# AUX_power_board.net
KiCad netlist of a schematic drawn in EAGLE
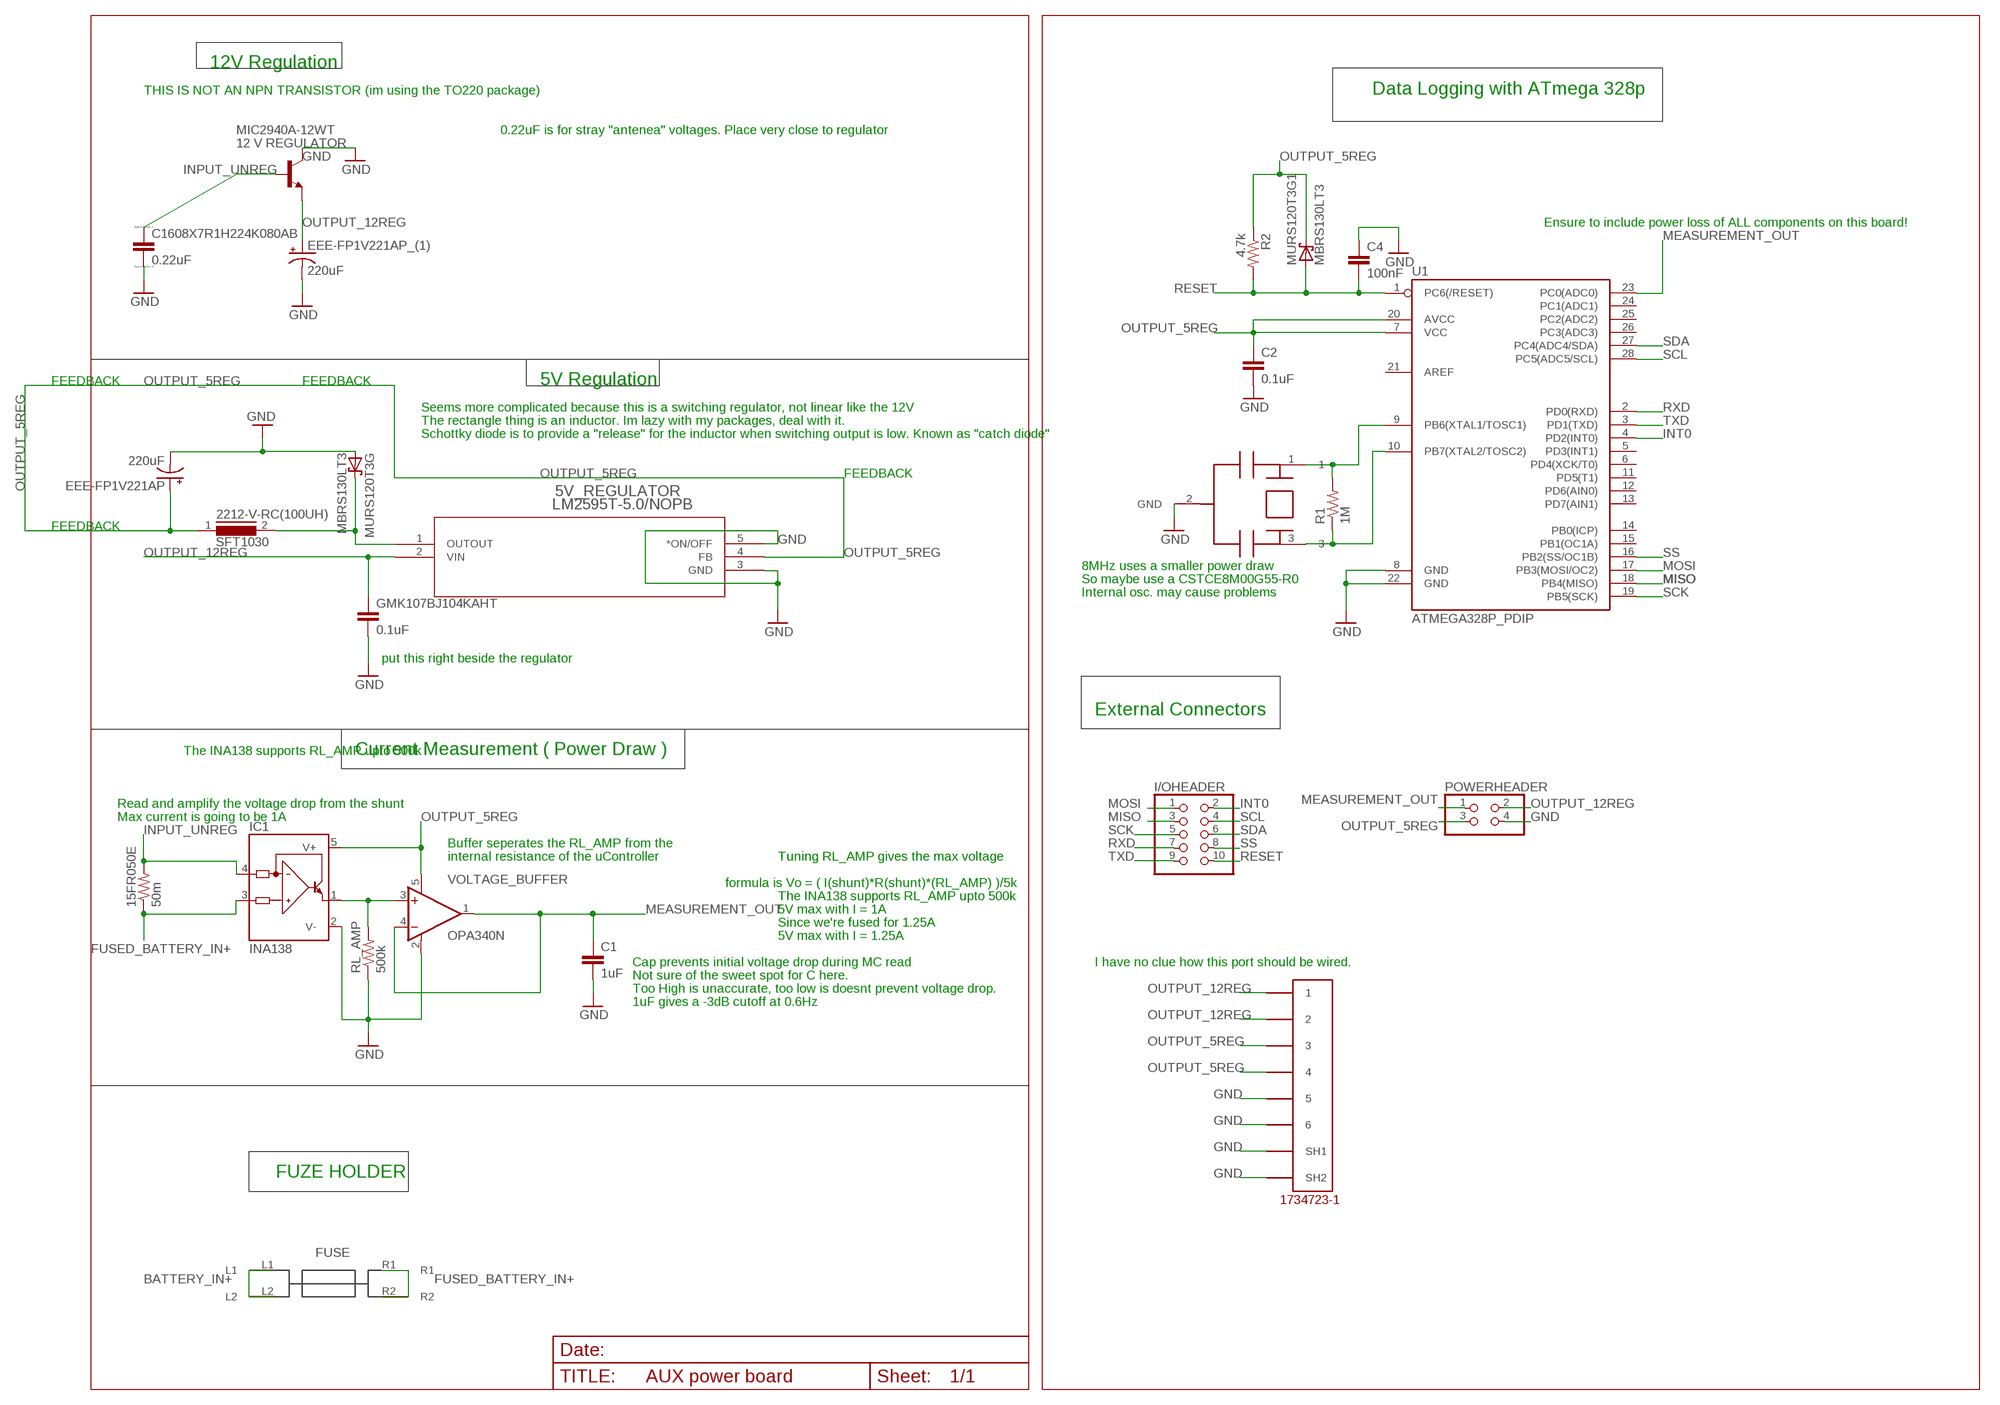
[diagram p0: schematic, sheet 1]

(export (version "E")
  (design (tool "Eeschema 10.0.6"))
  (components
    (comp (ref "5V_REGULATOR")
      (value "LM2595T-5.0/NOPB")
      (footprint "eagle-import:T05D")
      (fields
        (field (name "MANUFACTURER_PART_NUMBER") "LM2595T50")
        (field (name "COPYRIGHT") "Copyright C 2015 Accelerated Designs. All rights reserved")
      )
      (libsource (lib "eagle-import") (part "LM2595T-5.0/NOPB"))
    )
    (comp (ref "15FR050E")
      (value "50m")
      (footprint "eagle-import:0617_22")
      (libsource (lib "eagle-import") (part "resistor_R-US_0617/22"))
    )
    (comp (ref "2212-V-RC(100UH)")
      (value "SFT1030")
      (footprint "eagle-import:SFT1030")
      (libsource (lib "eagle-import") (part "SFT1030"))
    )
    (comp (ref "C1")
      (value "1uF")
      (footprint "eagle-import:C0603")
      (libsource (lib "eagle-import") (part "resistor_C-EUC0603"))
    )
    (comp (ref "C2")
      (value "0.1uF")
      (footprint "eagle-import:C0603")
      (libsource (lib "eagle-import") (part "resistor_C-EUC0603"))
    )
    (comp (ref "C4")
      (value "100nF")
      (footprint "eagle-import:C0603")
      (libsource (lib "eagle-import") (part "C-EUC0603"))
    )
    (comp (ref "C1608X7R1H224K080AB")
      (value "0.22uF")
      (footprint "eagle-import:C0603")
      (libsource (lib "eagle-import") (part "CC0603"))
    )
    (comp (ref "EEE-FP1V221AP")
      (value "220uF")
      (footprint "eagle-import:175TMP-0808")
      (libsource (lib "eagle-import") (part "CPOL-US175TMP-0808"))
    )
    (comp (ref "EEE-FP1V221AP_(1)")
      (value "220uF")
      (footprint "eagle-import:175TMP-0808")
      (libsource (lib "eagle-import") (part "CPOL-US175TMP-0808"))
    )
    (comp (ref "GMK107BJ104KAHT")
      (value "0.1uF")
      (footprint "eagle-import:C0603")
      (libsource (lib "eagle-import") (part "C-EUC0603"))
    )
    (comp (ref "I/OHEADER")
      (value "PINHD-2X5")
      (footprint "eagle-import:2X05")
      (libsource (lib "eagle-import") (part "PINHD-2X5"))
    )
    (comp (ref "IC1")
      (value "INA138")
      (footprint "eagle-import:SOT23-5")
      (fields (field (name "MF") "TEXAS INSTRUMENTS") (field (name "MPN") "INA138NA/250"))
      (libsource (lib "eagle-import") (part "INA138"))
    )
    (comp (ref "MIC2940A-12WT")
      (value "12 V REGULATOR")
      (footprint "eagle-import:TO220")
      (libsource (lib "eagle-import") (part "-NPN-TO220"))
    )
    (comp (ref "MINIBLADE")
      (value "3568")
      (footprint "eagle-import:3568")
      (libsource (lib "eagle-import") (part "3568"))
    )
    (comp (ref "MURS120T3G")
      (value "MBRS130LT3")
      (footprint "eagle-import:SMB")
      (libsource (lib "eagle-import") (part "MBRS130LT3"))
    )
    (comp (ref "MURS120T3G1")
      (value "MBRS130LT3")
      (footprint "eagle-import:SMB")
      (libsource (lib "eagle-import") (part "MBRS130LT3"))
    )
    (comp (ref "POWERHEADER")
      (value "PINHD-2X2")
      (footprint "eagle-import:2X02")
      (libsource (lib "eagle-import") (part "PINHD-2X2"))
    )
    (comp (ref "R1")
      (value "1M")
      (footprint "eagle-import:R0603")
      (libsource (lib "eagle-import") (part "R-US_R0603"))
    )
    (comp (ref "R2")
      (value "4.7k")
      (footprint "eagle-import:R0603")
      (libsource (lib "eagle-import") (part "resistor_R-US_R0603"))
    )
    (comp (ref "RL_AMP")
      (value "500k")
      (footprint "eagle-import:R0603")
      (libsource (lib "eagle-import") (part "resistor_R-US_R0603"))
    )
    (comp (ref "U$1")
      (value "CSTCE16M0V53-R0")
      (footprint "eagle-import:RESONATOR")
      (libsource (lib "eagle-import") (part "CSTCE16M0V53-R0"))
    )
    (comp (ref "U$3")
      (value "5555140-6")
      (footprint "eagle-import:1734723-1_RJ11")
      (libsource (lib "eagle-import") (part "5555140-6"))
    )
    (comp (ref "U1")
      (value "ATMEGA328P_PDIP")
      (footprint "eagle-import:DIL28-3")
      (libsource (lib "eagle-import") (part "ATMEGA328P_PDIP"))
    )
    (comp (ref "VOLTAGE_BUFFER")
      (value "OPA340N")
      (footprint "eagle-import:SOT23-5")
      (fields (field (name "MPN") "OPA340NA/3KG4"))
      (libsource (lib "eagle-import") (part "OPA340N"))
    )
  )
  (nets
    (net (code "1") (name "/BATTERY_IN+") (class "Default")
      (node (ref "MINIBLADE") (pin "L1") (pinfunction "L1_L1") (pintype "bidirectional"))
      (node (ref "MINIBLADE") (pin "L2") (pinfunction "L2_L2") (pintype "bidirectional"))
    )
    (net (code "2") (name "/FUSED_BATTERY_IN+") (class "Default")
      (node (ref "15FR050E") (pin "1") (pinfunction "1_1") (pintype "passive"))
      (node (ref "IC1") (pin "3") (pinfunction "IN+_3") (pintype "input"))
      (node (ref "MINIBLADE") (pin "R1") (pinfunction "R1_R1") (pintype "bidirectional"))
      (node (ref "MINIBLADE") (pin "R2") (pinfunction "R2_R2") (pintype "bidirectional"))
    )
    (net (code "3") (name "/INPUT_UNREG") (class "Default")
      (node (ref "15FR050E") (pin "2") (pinfunction "2_2") (pintype "passive"))
      (node (ref "C1608X7R1H224K080AB") (pin "1") (pinfunction "1_1") (pintype "passive"))
      (node (ref "IC1") (pin "4") (pinfunction "IN-_4") (pintype "input"))
      (node (ref "MIC2940A-12WT") (pin "1") (pinfunction "B_1") (pintype "passive"))
    )
    (net (code "4") (name "/INT0") (class "Default")
      (node (ref "I/OHEADER") (pin "2") (pinfunction "2_2") (pintype "passive"))
      (node (ref "U1") (pin "4") (pinfunction "PD2(INT0)_4") (pintype "bidirectional"))
    )
    (net (code "5") (name "/MEASUREMENT_OUT") (class "Default")
      (node (ref "C1") (pin "1") (pinfunction "1_1") (pintype "passive"))
      (node (ref "POWERHEADER") (pin "1") (pinfunction "1_1") (pintype "passive"))
      (node (ref "U1") (pin "23") (pinfunction "PC0(ADC0)_23") (pintype "bidirectional"))
      (node (ref "VOLTAGE_BUFFER") (pin "1") (pinfunction "OUT_1") (pintype "output"))
      (node (ref "VOLTAGE_BUFFER") (pin "4") (pinfunction "-IN_4") (pintype "input"))
    )
    (net (code "6") (name "/MISO") (class "Default")
      (node (ref "I/OHEADER") (pin "3") (pinfunction "3_3") (pintype "passive"))
      (node (ref "U1") (pin "18") (pinfunction "PB4(MISO)_18") (pintype "bidirectional"))
    )
    (net (code "7") (name "/MOSI") (class "Default")
      (node (ref "I/OHEADER") (pin "1") (pinfunction "1_1") (pintype "passive"))
      (node (ref "U1") (pin "17") (pinfunction "PB3(MOSI/OC2)_17") (pintype "bidirectional"))
    )
    (net (code "8") (name "/OUTPUT_5REG") (class "Default")
      (node (ref "2212-V-RC(100UH)") (pin "1") (pinfunction "1_1") (pintype "passive"))
      (node (ref "5V_REGULATOR") (pin "4") (pinfunction "FB_4") (pintype "passive"))
      (node (ref "C2") (pin "1") (pinfunction "1_1") (pintype "passive"))
      (node (ref "EEE-FP1V221AP") (pin "+") (pinfunction "+_+") (pintype "passive"))
      (node (ref "IC1") (pin "5") (pinfunction "V+_5") (pintype "power_in"))
      (node (ref "MURS120T3G1") (pin "C") (pinfunction "C_C") (pintype "passive"))
      (node (ref "POWERHEADER") (pin "3") (pinfunction "3_3") (pintype "passive"))
      (node (ref "R2") (pin "1") (pinfunction "1_1") (pintype "passive"))
      (node (ref "U$3") (pin "3") (pinfunction "3_3") (pintype "bidirectional"))
      (node (ref "U$3") (pin "4") (pinfunction "4_4") (pintype "bidirectional"))
      (node (ref "U1") (pin "20") (pinfunction "AVCC_20") (pintype "bidirectional"))
      (node (ref "U1") (pin "7") (pinfunction "VCC_7") (pintype "bidirectional"))
      (node (ref "VOLTAGE_BUFFER") (pin "5") (pinfunction "V+_5") (pintype "power_in"))
    )
    (net (code "9") (name "/OUTPUT_12REG") (class "Default")
      (node (ref "5V_REGULATOR") (pin "2") (pinfunction "VIN_2") (pintype "input"))
      (node (ref "EEE-FP1V221AP_(1)") (pin "+") (pinfunction "+_+") (pintype "passive"))
      (node (ref "GMK107BJ104KAHT") (pin "1") (pinfunction "1_1") (pintype "passive"))
      (node (ref "MIC2940A-12WT") (pin "3") (pinfunction "E_3") (pintype "passive"))
      (node (ref "POWERHEADER") (pin "2") (pinfunction "2_2") (pintype "passive"))
      (node (ref "U$3") (pin "1") (pinfunction "1_1") (pintype "bidirectional"))
      (node (ref "U$3") (pin "2") (pinfunction "2_2") (pintype "bidirectional"))
    )
    (net (code "10") (name "/RESET") (class "Default")
      (node (ref "C4") (pin "2") (pinfunction "2_2") (pintype "passive"))
      (node (ref "I/OHEADER") (pin "10") (pinfunction "10_10") (pintype "passive"))
      (node (ref "MURS120T3G1") (pin "A") (pinfunction "A_A") (pintype "passive"))
      (node (ref "R2") (pin "2") (pinfunction "2_2") (pintype "passive"))
      (node (ref "U1") (pin "1") (pinfunction "PC6(/RESET)_1") (pintype "bidirectional"))
    )
    (net (code "11") (name "/RXD") (class "Default")
      (node (ref "I/OHEADER") (pin "7") (pinfunction "7_7") (pintype "passive"))
      (node (ref "U1") (pin "2") (pinfunction "PD0(RXD)_2") (pintype "bidirectional"))
    )
    (net (code "12") (name "/SCK") (class "Default")
      (node (ref "I/OHEADER") (pin "5") (pinfunction "5_5") (pintype "passive"))
      (node (ref "U1") (pin "19") (pinfunction "PB5(SCK)_19") (pintype "bidirectional"))
    )
    (net (code "13") (name "/SCL") (class "Default")
      (node (ref "I/OHEADER") (pin "4") (pinfunction "4_4") (pintype "passive"))
      (node (ref "U1") (pin "28") (pinfunction "PC5(ADC5/SCL)_28") (pintype "bidirectional"))
    )
    (net (code "14") (name "/SDA") (class "Default")
      (node (ref "I/OHEADER") (pin "6") (pinfunction "6_6") (pintype "passive"))
      (node (ref "U1") (pin "27") (pinfunction "PC4(ADC4/SDA)_27") (pintype "bidirectional"))
    )
    (net (code "15") (name "/SS") (class "Default")
      (node (ref "I/OHEADER") (pin "8") (pinfunction "8_8") (pintype "passive"))
      (node (ref "U1") (pin "16") (pinfunction "PB2(SS/OC1B)_16") (pintype "bidirectional"))
    )
    (net (code "16") (name "/TXD") (class "Default")
      (node (ref "I/OHEADER") (pin "9") (pinfunction "9_9") (pintype "passive"))
      (node (ref "U1") (pin "3") (pinfunction "PD1(TXD)_3") (pintype "bidirectional"))
    )
    (net (code "17") (name "GND") (class "Default")
      (node (ref "5V_REGULATOR") (pin "3") (pinfunction "GND_3") (pintype "passive"))
      (node (ref "5V_REGULATOR") (pin "5") (pinfunction "*ON/OFF_5") (pintype "passive"))
      (node (ref "C1") (pin "2") (pinfunction "2_2") (pintype "passive"))
      (node (ref "C1608X7R1H224K080AB") (pin "2") (pinfunction "2_2") (pintype "passive"))
      (node (ref "C2") (pin "2") (pinfunction "2_2") (pintype "passive"))
      (node (ref "C4") (pin "1") (pinfunction "1_1") (pintype "passive"))
      (node (ref "EEE-FP1V221AP") (pin "-") (pinfunction "-_-") (pintype "passive"))
      (node (ref "EEE-FP1V221AP_(1)") (pin "-") (pinfunction "-_-") (pintype "passive"))
      (node (ref "GMK107BJ104KAHT") (pin "2") (pinfunction "2_2") (pintype "passive"))
      (node (ref "IC1") (pin "2") (pinfunction "V-_2") (pintype "power_in"))
      (node (ref "MIC2940A-12WT") (pin "2") (pinfunction "C_2") (pintype "passive"))
      (node (ref "MURS120T3G") (pin "A") (pinfunction "A_A") (pintype "passive"))
      (node (ref "POWERHEADER") (pin "4") (pinfunction "4_4") (pintype "passive"))
      (node (ref "RL_AMP") (pin "1") (pinfunction "1_1") (pintype "passive"))
      (node (ref "U$3") (pin "5") (pinfunction "5_5") (pintype "bidirectional"))
      (node (ref "U$3") (pin "6") (pinfunction "6_6") (pintype "bidirectional"))
      (node (ref "U$3") (pin "SH1") (pinfunction "SH1_SH1") (pintype "bidirectional"))
      (node (ref "U$3") (pin "SH2") (pinfunction "SH2_SH2") (pintype "bidirectional"))
      (node (ref "U1") (pin "22") (pinfunction "GND_22") (pintype "bidirectional"))
      (node (ref "U1") (pin "8") (pinfunction "GND_8") (pintype "bidirectional"))
      (node (ref "VOLTAGE_BUFFER") (pin "2") (pinfunction "V-_2") (pintype "power_in"))
    )
    (net (code "18") (name "Net-(5V_REGULATOR-OUTOUT)") (class "Default")
      (node (ref "2212-V-RC(100UH)") (pin "2") (pinfunction "2_2") (pintype "passive"))
      (node (ref "5V_REGULATOR") (pin "1") (pinfunction "OUTOUT_1") (pintype "output"))
      (node (ref "MURS120T3G") (pin "C") (pinfunction "C_C") (pintype "passive"))
    )
    (net (code "19") (name "Net-(IC1-OUT)") (class "Default")
      (node (ref "IC1") (pin "1") (pinfunction "OUT_1") (pintype "output"))
      (node (ref "RL_AMP") (pin "2") (pinfunction "2_2") (pintype "passive"))
      (node (ref "VOLTAGE_BUFFER") (pin "3") (pinfunction "+IN_3") (pintype "input"))
    )
    (net (code "20") (name "Net-(U1-PB6(XTAL1{slash}TOSC1))") (class "Default")
      (node (ref "R1") (pin "2") (pinfunction "2_2") (pintype "passive"))
      (node (ref "U1") (pin "9") (pinfunction "PB6(XTAL1/TOSC1)_9") (pintype "bidirectional"))
    )
    (net (code "21") (name "Net-(U1-PB7(XTAL2{slash}TOSC2))") (class "Default")
      (node (ref "R1") (pin "1") (pinfunction "1_1") (pintype "passive"))
      (node (ref "U1") (pin "10") (pinfunction "PB7(XTAL2/TOSC2)_10") (pintype "bidirectional"))
    )
    (net (code "22") (name "unconnected-(U$1-GND-Pad2)") (class "Default")
      (node (ref "U$1") (pin "2") (pinfunction "GND_2") (pintype "bidirectional"))
    )
    (net (code "23") (name "unconnected-(U$1-Pad1)") (class "Default")
      (node (ref "U$1") (pin "1") (pinfunction "1_1") (pintype "bidirectional"))
    )
    (net (code "24") (name "unconnected-(U$1-Pad3)") (class "Default")
      (node (ref "U$1") (pin "3") (pinfunction "3_3") (pintype "bidirectional"))
    )
    (net (code "25") (name "unconnected-(U1-AREF-Pad21)") (class "Default")
      (node (ref "U1") (pin "21") (pinfunction "AREF_21") (pintype "bidirectional"))
    )
    (net (code "26") (name "unconnected-(U1-PB0(ICP)-Pad14)") (class "Default")
      (node (ref "U1") (pin "14") (pinfunction "PB0(ICP)_14") (pintype "bidirectional"))
    )
    (net (code "27") (name "unconnected-(U1-PB1(OC1A)-Pad15)") (class "Default")
      (node (ref "U1") (pin "15") (pinfunction "PB1(OC1A)_15") (pintype "bidirectional"))
    )
    (net (code "28") (name "unconnected-(U1-PC1(ADC1)-Pad24)") (class "Default")
      (node (ref "U1") (pin "24") (pinfunction "PC1(ADC1)_24") (pintype "bidirectional"))
    )
    (net (code "29") (name "unconnected-(U1-PC2(ADC2)-Pad25)") (class "Default")
      (node (ref "U1") (pin "25") (pinfunction "PC2(ADC2)_25") (pintype "bidirectional"))
    )
    (net (code "30") (name "unconnected-(U1-PC3(ADC3)-Pad26)") (class "Default")
      (node (ref "U1") (pin "26") (pinfunction "PC3(ADC3)_26") (pintype "bidirectional"))
    )
    (net (code "31") (name "unconnected-(U1-PD3(INT1)-Pad5)") (class "Default")
      (node (ref "U1") (pin "5") (pinfunction "PD3(INT1)_5") (pintype "bidirectional"))
    )
    (net (code "32") (name "unconnected-(U1-PD4(XCK{slash}T0)-Pad6)") (class "Default")
      (node (ref "U1") (pin "6") (pinfunction "PD4(XCK/T0)_6") (pintype "bidirectional"))
    )
    (net (code "33") (name "unconnected-(U1-PD5(T1)-Pad11)") (class "Default")
      (node (ref "U1") (pin "11") (pinfunction "PD5(T1)_11") (pintype "bidirectional"))
    )
    (net (code "34") (name "unconnected-(U1-PD6(AIN0)-Pad12)") (class "Default")
      (node (ref "U1") (pin "12") (pinfunction "PD6(AIN0)_12") (pintype "bidirectional"))
    )
    (net (code "35") (name "unconnected-(U1-PD7(AIN1)-Pad13)") (class "Default")
      (node (ref "U1") (pin "13") (pinfunction "PD7(AIN1)_13") (pintype "bidirectional"))
    )
  )
)
